# ASM4004.net
KiCad netlist of a schematic drawn in EAGLE
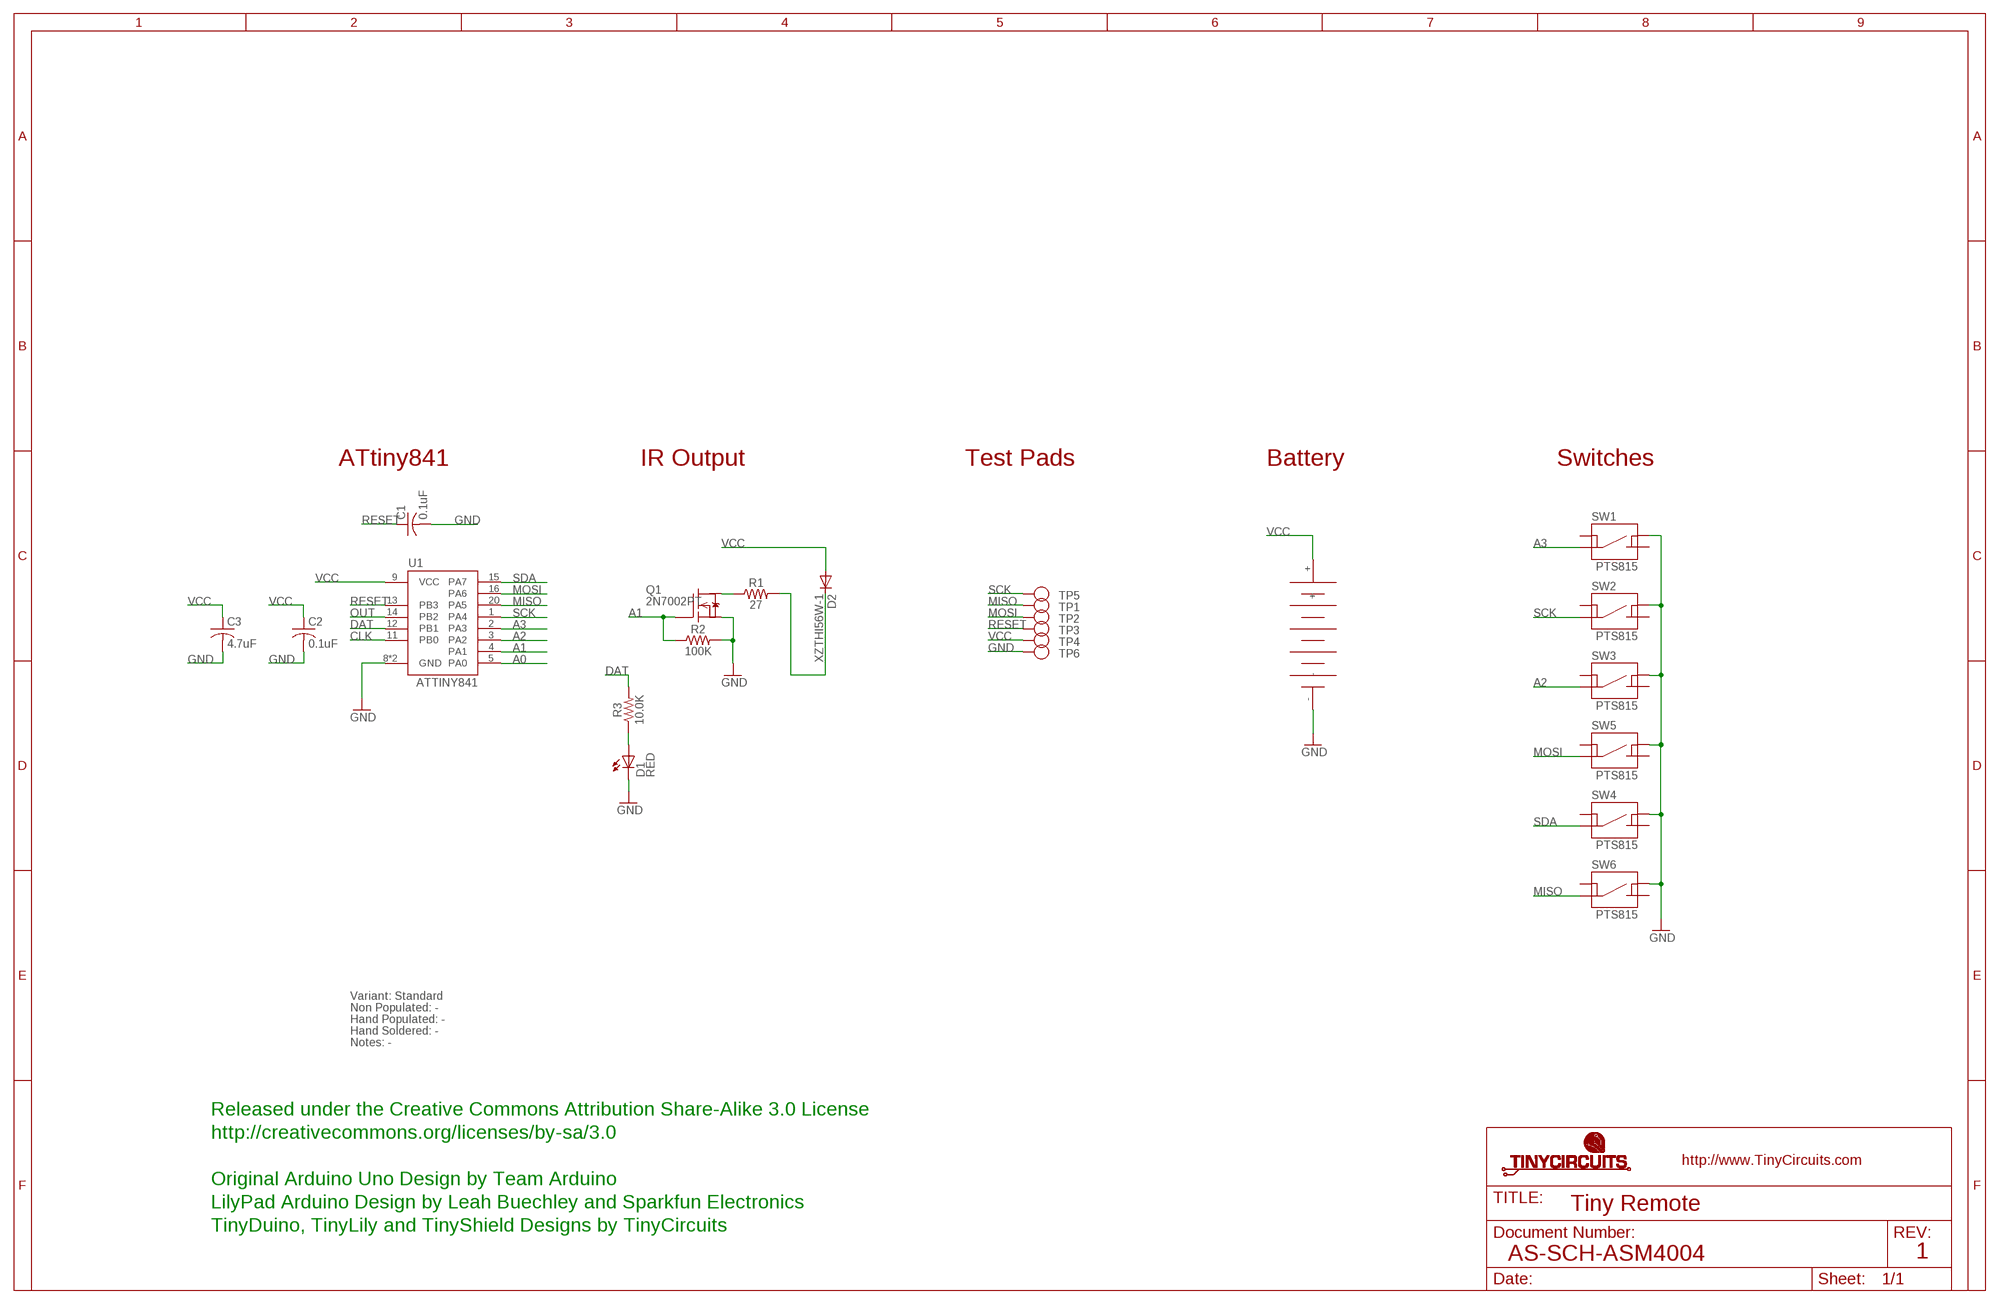
[diagram p0: schematic, sheet 1]

(export (version "E")
  (design (tool "Eeschema 10.0.6"))
  (components
    (comp (ref "C1")
      (value "0.1uF")
      (footprint "eagle-import:C0402")
      (fields (field (name "PARTNO") "AS-ITM-00008") (field (name "PARTNO_1") "AS-ITM-00008"))
      (libsource (lib "eagle-import") (part "AS-ITM-00008"))
    )
    (comp (ref "C2")
      (value "0.1uF")
      (footprint "eagle-import:C0402")
      (fields (field (name "PARTNO") "AS-ITM-00008"))
      (libsource (lib "eagle-import") (part "AS-ITM-00008"))
    )
    (comp (ref "C3")
      (value "4.7uF")
      (footprint "eagle-import:C0402")
      (fields (field (name "PARTNO") "AS-ITM-00242") (field (name "PARTNO_1") "AS-ITM-00242"))
      (libsource (lib "eagle-import") (part "AS-ITM-00242"))
    )
    (comp (ref "D1")
      (value "RED")
      (footprint "eagle-import:0402_LED")
      (fields (field (name "PARTNO") "AS-ITM-00057") (field (name "PARTNO_1") "AS-ITM-00057"))
      (libsource (lib "eagle-import") (part "AS-ITM-00057"))
    )
    (comp (ref "D2")
      (value "XZTHI56W-1")
      (footprint "eagle-import:LED_SIDE_3.0X1.0")
      (fields (field (name "PARTNO") "AS-ITM-00551") (field (name "PARTNO_1") "AS-ITM-00551"))
      (libsource (lib "eagle-import") (part "AS-ITM-00551"))
    )
    (comp (ref "J2")
      (value "1225")
      (footprint "eagle-import:COIN_1220_SMD")
      (fields (field (name "PARTNO") "AS-ITM-00468") (field (name "PARTNO_1") "AS-ITM-00468"))
      (libsource (lib "eagle-import") (part "AS-ITM-00468"))
    )
    (comp (ref "Q1")
      (value "2N7002PT")
      (footprint "eagle-import:SOT-416")
      (fields (field (name "PARTNO") "AS-ITM-00110"))
      (libsource (lib "eagle-import") (part "AS-ITM-00110"))
    )
    (comp (ref "R1")
      (value "27")
      (footprint "eagle-import:0402")
      (fields (field (name "PARTNO") "AS-ITM-00240") (field (name "PARTNO_1") "AS-ITM-00240"))
      (libsource (lib "eagle-import") (part "AS-ITM-00240"))
    )
    (comp (ref "R2")
      (value "100K")
      (footprint "eagle-import:0402")
      (fields (field (name "PARTNO") "AS-ITM-00004"))
      (libsource (lib "eagle-import") (part "AS-ITM-00004"))
    )
    (comp (ref "R3")
      (value "10.0K")
      (footprint "eagle-import:0402")
      (fields (field (name "PARTNO") "AS-ITM-00032") (field (name "PARTNO_1") "AS-ITM-00032"))
      (libsource (lib "eagle-import") (part "AS-ITM-00032"))
    )
    (comp (ref "SW1")
      (value "PTS815")
      (footprint "eagle-import:PTS815")
      (fields (field (name "PARTNO") "AS-ITM-00544") (field (name "PARTNO_1") "AS-ITM-00544"))
      (libsource (lib "eagle-import") (part "AS-ITM-00544"))
    )
    (comp (ref "SW2")
      (value "PTS815")
      (footprint "eagle-import:PTS815")
      (fields (field (name "PARTNO") "AS-ITM-00544") (field (name "PARTNO_1") "AS-ITM-00544"))
      (libsource (lib "eagle-import") (part "AS-ITM-00544"))
    )
    (comp (ref "SW3")
      (value "PTS815")
      (footprint "eagle-import:PTS815")
      (fields (field (name "PARTNO") "AS-ITM-00544") (field (name "PARTNO_1") "AS-ITM-00544"))
      (libsource (lib "eagle-import") (part "AS-ITM-00544"))
    )
    (comp (ref "SW4")
      (value "PTS815")
      (footprint "eagle-import:PTS815")
      (fields (field (name "PARTNO") "AS-ITM-00544") (field (name "PARTNO_1") "AS-ITM-00544"))
      (libsource (lib "eagle-import") (part "AS-ITM-00544"))
    )
    (comp (ref "SW5")
      (value "PTS815")
      (footprint "eagle-import:PTS815")
      (fields (field (name "PARTNO") "AS-ITM-00544") (field (name "PARTNO_1") "AS-ITM-00544"))
      (libsource (lib "eagle-import") (part "AS-ITM-00544"))
    )
    (comp (ref "SW6")
      (value "PTS815")
      (footprint "eagle-import:PTS815")
      (fields (field (name "PARTNO") "AS-ITM-00544") (field (name "PARTNO_1") "AS-ITM-00544"))
      (libsource (lib "eagle-import") (part "AS-ITM-00544"))
    )
    (comp (ref "TP1")
      (value "TEST_POINT")
      (footprint "eagle-import:TEST_POINT_1MM")
      (libsource (lib "eagle-import") (part "TEST_POINT"))
    )
    (comp (ref "TP2")
      (value "TEST_POINT")
      (footprint "eagle-import:TEST_POINT_1MM")
      (libsource (lib "eagle-import") (part "TEST_POINT"))
    )
    (comp (ref "TP3")
      (value "TEST_POINT")
      (footprint "eagle-import:TEST_POINT_1MM")
      (libsource (lib "eagle-import") (part "TEST_POINT"))
    )
    (comp (ref "TP4")
      (value "TEST_POINT")
      (footprint "eagle-import:TEST_POINT_1MM")
      (libsource (lib "eagle-import") (part "TEST_POINT"))
    )
    (comp (ref "TP5")
      (value "TEST_POINT")
      (footprint "eagle-import:TEST_POINT_1MM")
      (libsource (lib "eagle-import") (part "TEST_POINT"))
    )
    (comp (ref "TP6")
      (value "TEST_POINT")
      (footprint "eagle-import:TEST_POINT_1MM")
      (libsource (lib "eagle-import") (part "TEST_POINT"))
    )
    (comp (ref "U1")
      (value "ATTINY841")
      (footprint "eagle-import:VQFN-20")
      (fields (field (name "PARTNO") "AS-ITM-00255"))
      (libsource (lib "eagle-import") (part "AS-ITM-00255"))
    )
  )
  (nets
    (net (code "1") (name "/A0") (class "Default")
      (node (ref "U1") (pin "5") (pinfunction "PA0_5") (pintype "bidirectional"))
    )
    (net (code "2") (name "/A1") (class "Default")
      (node (ref "Q1") (pin "1") (pinfunction "G_1") (pintype "passive"))
      (node (ref "R2") (pin "1") (pinfunction "1_1") (pintype "passive"))
      (node (ref "U1") (pin "4") (pinfunction "PA1_4") (pintype "bidirectional"))
    )
    (net (code "3") (name "/A2") (class "Default")
      (node (ref "SW3") (pin "1") (pinfunction "1_1") (pintype "bidirectional"))
      (node (ref "U1") (pin "3") (pinfunction "PA2_3") (pintype "bidirectional"))
    )
    (net (code "4") (name "/A3") (class "Default")
      (node (ref "SW1") (pin "1") (pinfunction "1_1") (pintype "bidirectional"))
      (node (ref "U1") (pin "2") (pinfunction "PA3_2") (pintype "bidirectional"))
    )
    (net (code "5") (name "/CLK") (class "Default")
      (node (ref "U1") (pin "11") (pinfunction "PB0_11") (pintype "bidirectional"))
    )
    (net (code "6") (name "/DAT") (class "Default")
      (node (ref "R3") (pin "2") (pinfunction "2_2") (pintype "passive"))
      (node (ref "U1") (pin "12") (pinfunction "PB1_12") (pintype "bidirectional"))
    )
    (net (code "7") (name "/MISO") (class "Default")
      (node (ref "SW6") (pin "1") (pinfunction "1_1") (pintype "bidirectional"))
      (node (ref "TP1") (pin "P$1") (pinfunction "1_P$1") (pintype "bidirectional"))
      (node (ref "U1") (pin "20") (pinfunction "PA5_20") (pintype "bidirectional"))
    )
    (net (code "8") (name "/MOSI") (class "Default")
      (node (ref "SW5") (pin "1") (pinfunction "1_1") (pintype "bidirectional"))
      (node (ref "TP2") (pin "P$1") (pinfunction "1_P$1") (pintype "bidirectional"))
      (node (ref "U1") (pin "16") (pinfunction "PA6_16") (pintype "bidirectional"))
    )
    (net (code "9") (name "/OUT") (class "Default")
      (node (ref "U1") (pin "14") (pinfunction "PB2_14") (pintype "bidirectional"))
    )
    (net (code "10") (name "/RESET") (class "Default")
      (node (ref "C1") (pin "1") (pinfunction "1_1") (pintype "passive"))
      (node (ref "TP3") (pin "P$1") (pinfunction "1_P$1") (pintype "bidirectional"))
      (node (ref "U1") (pin "13") (pinfunction "PB3_13") (pintype "bidirectional"))
    )
    (net (code "11") (name "/SCK") (class "Default")
      (node (ref "SW2") (pin "1") (pinfunction "1_1") (pintype "bidirectional"))
      (node (ref "TP5") (pin "P$1") (pinfunction "1_P$1") (pintype "bidirectional"))
      (node (ref "U1") (pin "1") (pinfunction "PA4_1") (pintype "bidirectional"))
    )
    (net (code "12") (name "/SDA") (class "Default")
      (node (ref "SW4") (pin "1") (pinfunction "1_1") (pintype "bidirectional"))
      (node (ref "U1") (pin "15") (pinfunction "PA7_15") (pintype "bidirectional"))
    )
    (net (code "13") (name "/VCC") (class "Default")
      (node (ref "C2") (pin "1") (pinfunction "1_1") (pintype "passive"))
      (node (ref "C3") (pin "1") (pinfunction "1_1") (pintype "passive"))
      (node (ref "D2") (pin "A") (pinfunction "A_A") (pintype "passive"))
      (node (ref "J2") (pin "+") (pinfunction "+_+") (pintype "bidirectional"))
      (node (ref "TP4") (pin "P$1") (pinfunction "1_P$1") (pintype "bidirectional"))
      (node (ref "U1") (pin "9") (pinfunction "VCC_9") (pintype "bidirectional"))
    )
    (net (code "14") (name "GND") (class "Default")
      (node (ref "C1") (pin "2") (pinfunction "2_2") (pintype "passive"))
      (node (ref "C2") (pin "2") (pinfunction "2_2") (pintype "passive"))
      (node (ref "C3") (pin "2") (pinfunction "2_2") (pintype "passive"))
      (node (ref "D1") (pin "2") (pinfunction "C_2") (pintype "passive"))
      (node (ref "J2") (pin "-") (pinfunction "-_-") (pintype "bidirectional"))
      (node (ref "Q1") (pin "2") (pinfunction "S_2") (pintype "passive"))
      (node (ref "R2") (pin "2") (pinfunction "2_2") (pintype "passive"))
      (node (ref "SW1") (pin "4") (pinfunction "4_4") (pintype "bidirectional"))
      (node (ref "SW2") (pin "4") (pinfunction "4_4") (pintype "bidirectional"))
      (node (ref "SW3") (pin "4") (pinfunction "4_4") (pintype "bidirectional"))
      (node (ref "SW4") (pin "4") (pinfunction "4_4") (pintype "bidirectional"))
      (node (ref "SW5") (pin "4") (pinfunction "4_4") (pintype "bidirectional"))
      (node (ref "SW6") (pin "4") (pinfunction "4_4") (pintype "bidirectional"))
      (node (ref "TP6") (pin "P$1") (pinfunction "1_P$1") (pintype "bidirectional"))
      (node (ref "U1") (pin "8") (pinfunction "GND_8") (pintype "bidirectional"))
      (node (ref "U1") (pin "PAD") (pinfunction "GND_PAD") (pintype "bidirectional"))
    )
    (net (code "15") (name "Net-(D1-A)") (class "Default")
      (node (ref "D1") (pin "1") (pinfunction "A_1") (pintype "passive"))
      (node (ref "R3") (pin "1") (pinfunction "1_1") (pintype "passive"))
    )
    (net (code "16") (name "Net-(D2-PadC)") (class "Default")
      (node (ref "D2") (pin "C") (pinfunction "C_C") (pintype "passive"))
      (node (ref "R1") (pin "2") (pinfunction "2_2") (pintype "passive"))
    )
    (net (code "17") (name "Net-(Q1-D)") (class "Default")
      (node (ref "Q1") (pin "3") (pinfunction "D_3") (pintype "passive"))
      (node (ref "R1") (pin "1") (pinfunction "1_1") (pintype "passive"))
    )
    (net (code "18") (name "unconnected-(SW1-2-Pad3)") (class "Default")
      (node (ref "SW1") (pin "3") (pinfunction "2_3") (pintype "bidirectional"))
    )
    (net (code "19") (name "unconnected-(SW1-3-Pad2)") (class "Default")
      (node (ref "SW1") (pin "2") (pinfunction "3_2") (pintype "bidirectional"))
    )
    (net (code "20") (name "unconnected-(SW2-2-Pad3)") (class "Default")
      (node (ref "SW2") (pin "3") (pinfunction "2_3") (pintype "bidirectional"))
    )
    (net (code "21") (name "unconnected-(SW2-3-Pad2)") (class "Default")
      (node (ref "SW2") (pin "2") (pinfunction "3_2") (pintype "bidirectional"))
    )
    (net (code "22") (name "unconnected-(SW3-2-Pad3)") (class "Default")
      (node (ref "SW3") (pin "3") (pinfunction "2_3") (pintype "bidirectional"))
    )
    (net (code "23") (name "unconnected-(SW3-3-Pad2)") (class "Default")
      (node (ref "SW3") (pin "2") (pinfunction "3_2") (pintype "bidirectional"))
    )
    (net (code "24") (name "unconnected-(SW4-2-Pad3)") (class "Default")
      (node (ref "SW4") (pin "3") (pinfunction "2_3") (pintype "bidirectional"))
    )
    (net (code "25") (name "unconnected-(SW4-3-Pad2)") (class "Default")
      (node (ref "SW4") (pin "2") (pinfunction "3_2") (pintype "bidirectional"))
    )
    (net (code "26") (name "unconnected-(SW5-2-Pad3)") (class "Default")
      (node (ref "SW5") (pin "3") (pinfunction "2_3") (pintype "bidirectional"))
    )
    (net (code "27") (name "unconnected-(SW5-3-Pad2)") (class "Default")
      (node (ref "SW5") (pin "2") (pinfunction "3_2") (pintype "bidirectional"))
    )
    (net (code "28") (name "unconnected-(SW6-2-Pad3)") (class "Default")
      (node (ref "SW6") (pin "3") (pinfunction "2_3") (pintype "bidirectional"))
    )
    (net (code "29") (name "unconnected-(SW6-3-Pad2)") (class "Default")
      (node (ref "SW6") (pin "2") (pinfunction "3_2") (pintype "bidirectional"))
    )
  )
)
